# ProjekITS_5.net
KiCad netlist of a schematic drawn in EAGLE
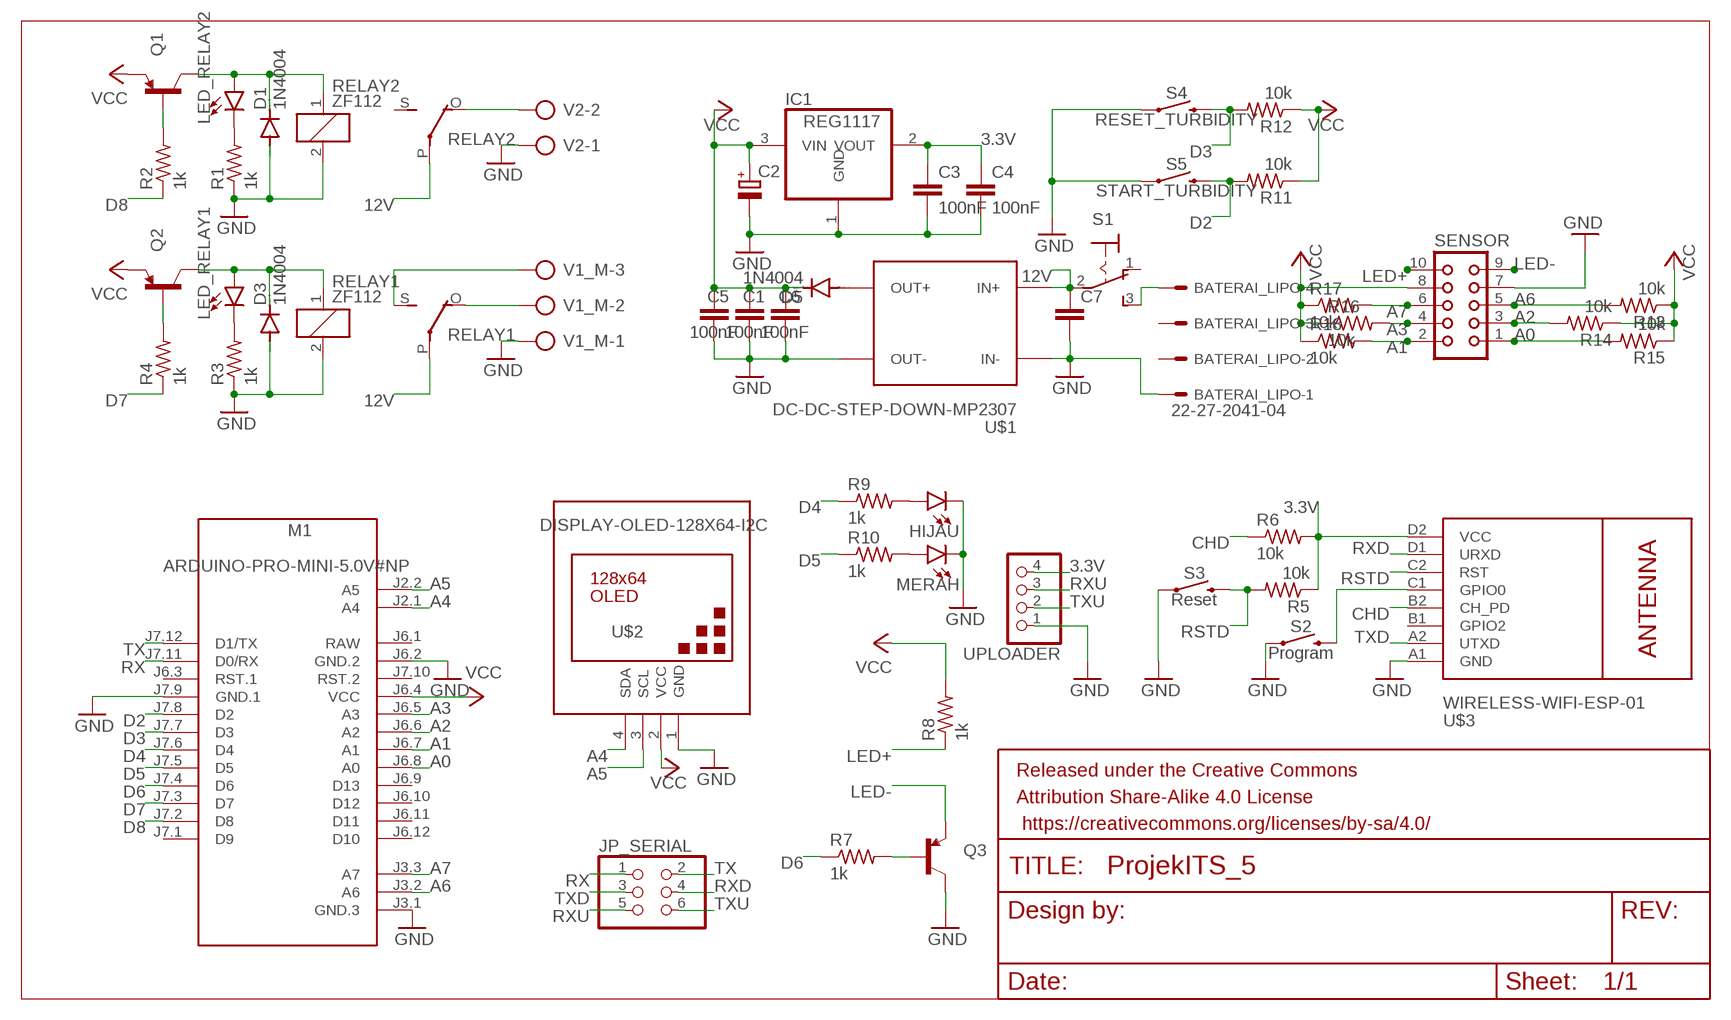
[diagram p0: schematic, sheet 1]

(export (version "E")
  (design (tool "Eeschema 10.0.6"))
  (components
    (comp (ref "BATERAI_LIPO")
      (value "22-27-2041-04")
      (footprint "eagle-import:6410-04")
      (fields (field (name "MF") "MOLEX"))
      (libsource (lib "eagle-import") (part "22-?-0427-2041"))
    )
    (comp (ref "C1")
      (value "100nF")
      (footprint "eagle-import:C0805K")
      (libsource (lib "eagle-import") (part "C-EUC0805K"))
    )
    (comp (ref "C2")
      (value "CPOL-EUCT3528")
      (footprint "eagle-import:CT3528")
      (libsource (lib "eagle-import") (part "CPOL-EUCT3528"))
    )
    (comp (ref "C3")
      (value "100nF")
      (footprint "eagle-import:C0805K")
      (libsource (lib "eagle-import") (part "C-EUC0805K"))
    )
    (comp (ref "C4")
      (value "100nF")
      (footprint "eagle-import:C0805K")
      (libsource (lib "eagle-import") (part "C-EUC0805K"))
    )
    (comp (ref "C5")
      (value "100nF")
      (footprint "eagle-import:C0805K")
      (libsource (lib "eagle-import") (part "C-EUC0805K"))
    )
    (comp (ref "C6")
      (value "100nF")
      (footprint "eagle-import:C0805K")
      (libsource (lib "eagle-import") (part "C-EUC0805K"))
    )
    (comp (ref "C7")
      (value "C-EU050-030X075")
      (footprint "eagle-import:C050-030X075")
      (libsource (lib "eagle-import") (part "C-EU050-030X075"))
    )
    (comp (ref "D1")
      (value "1N4004")
      (footprint "eagle-import:DO41-10")
      (libsource (lib "eagle-import") (part "1N4004"))
    )
    (comp (ref "D3")
      (value "1N4004")
      (footprint "eagle-import:DO41-10")
      (libsource (lib "eagle-import") (part "1N4004"))
    )
    (comp (ref "D5")
      (value "1N4004")
      (footprint "eagle-import:DO41-10")
      (libsource (lib "eagle-import") (part "1N4004"))
    )
    (comp (ref "FRAME1")
      (value "FRAME-LETTER")
      (footprint "eagle-import:CREATIVE_COMMONS")
      (libsource (lib "eagle-import") (part "FRAME-LETTER"))
    )
    (comp (ref "HIJAU")
      (value "LED5MM")
      (footprint "eagle-import:LED_5MM")
      (libsource (lib "eagle-import") (part "LED5MM"))
    )
    (comp (ref "IC1")
      (value "REG1117")
      (footprint "eagle-import:SOT223")
      (libsource (lib "eagle-import") (part "REG1117"))
    )
    (comp (ref "JP_SERIAL")
      (value "PINHD-2X3")
      (footprint "eagle-import:2X03")
      (libsource (lib "eagle-import") (part "PINHD-2X3"))
    )
    (comp (ref "LED_RELAY1")
      (value "LED3MM")
      (footprint "eagle-import:LED_3MM")
      (libsource (lib "eagle-import") (part "LED3MM"))
    )
    (comp (ref "LED_RELAY2")
      (value "LED3MM")
      (footprint "eagle-import:LED_3MM")
      (libsource (lib "eagle-import") (part "LED3MM"))
    )
    (comp (ref "M1")
      (value "ARDUINO-PRO-MINI-5.0V#NP")
      (footprint "eagle-import:ARDUINO-PRO-MINI#NP")
      (libsource (lib "eagle-import") (part "ARDUINO-PRO-MINI-#NP5.0V"))
    )
    (comp (ref "MERAH")
      (value "LED5MM")
      (footprint "eagle-import:LED_5MM")
      (libsource (lib "eagle-import") (part "LED5MM"))
    )
    (comp (ref "Q1")
      (value "TRANSISTOR_PNPSMD")
      (footprint "eagle-import:SOT23-3")
      (libsource (lib "eagle-import") (part "TRANSISTOR_PNPSMD"))
    )
    (comp (ref "Q2")
      (value "TRANSISTOR_PNPSMD")
      (footprint "eagle-import:SOT23-3")
      (libsource (lib "eagle-import") (part "TRANSISTOR_PNPSMD"))
    )
    (comp (ref "Q3")
      (value "TRANSISTOR_PNPSMD")
      (footprint "eagle-import:SOT23-3")
      (libsource (lib "eagle-import") (part "TRANSISTOR_PNPSMD"))
    )
    (comp (ref "R1")
      (value "1k")
      (footprint "eagle-import:R0805")
      (libsource (lib "eagle-import") (part "R-US_R0805"))
    )
    (comp (ref "R2")
      (value "1k")
      (footprint "eagle-import:R0805")
      (libsource (lib "eagle-import") (part "R-US_R0805"))
    )
    (comp (ref "R3")
      (value "1k")
      (footprint "eagle-import:R0805")
      (libsource (lib "eagle-import") (part "R-US_R0805"))
    )
    (comp (ref "R4")
      (value "1k")
      (footprint "eagle-import:R0805")
      (libsource (lib "eagle-import") (part "R-US_R0805"))
    )
    (comp (ref "R5")
      (value "10k")
      (footprint "eagle-import:R0805")
      (libsource (lib "eagle-import") (part "R-US_R0805"))
    )
    (comp (ref "R6")
      (value "10k")
      (footprint "eagle-import:R0805")
      (libsource (lib "eagle-import") (part "R-US_R0805"))
    )
    (comp (ref "R7")
      (value "1k")
      (footprint "eagle-import:R0805")
      (libsource (lib "eagle-import") (part "R-US_R0805"))
    )
    (comp (ref "R8")
      (value "1k")
      (footprint "eagle-import:R0805")
      (libsource (lib "eagle-import") (part "R-US_R0805"))
    )
    (comp (ref "R9")
      (value "1k")
      (footprint "eagle-import:R0805")
      (libsource (lib "eagle-import") (part "R-US_R0805"))
    )
    (comp (ref "R10")
      (value "1k")
      (footprint "eagle-import:R0805")
      (libsource (lib "eagle-import") (part "R-US_R0805"))
    )
    (comp (ref "R11")
      (value "10k")
      (footprint "eagle-import:R0805")
      (libsource (lib "eagle-import") (part "R-US_R0805"))
    )
    (comp (ref "R12")
      (value "10k")
      (footprint "eagle-import:R0805")
      (libsource (lib "eagle-import") (part "R-US_R0805"))
    )
    (comp (ref "R13")
      (value "10k")
      (footprint "eagle-import:R0805")
      (libsource (lib "eagle-import") (part "R-US_R0805"))
    )
    (comp (ref "R14")
      (value "10k")
      (footprint "eagle-import:R0805")
      (libsource (lib "eagle-import") (part "R-US_R0805"))
    )
    (comp (ref "R15")
      (value "10k")
      (footprint "eagle-import:R0805")
      (libsource (lib "eagle-import") (part "R-US_R0805"))
    )
    (comp (ref "R16")
      (value "10k")
      (footprint "eagle-import:R0805")
      (libsource (lib "eagle-import") (part "R-US_R0805"))
    )
    (comp (ref "R17")
      (value "10k")
      (footprint "eagle-import:R0805")
      (libsource (lib "eagle-import") (part "R-US_R0805"))
    )
    (comp (ref "R18")
      (value "10k")
      (footprint "eagle-import:R0805")
      (libsource (lib "eagle-import") (part "R-US_R0805"))
    )
    (comp (ref "RELAY1")
      (value "ZF112")
      (footprint "eagle-import:ZF112")
      (libsource (lib "eagle-import") (part "ZF112"))
    )
    (comp (ref "RELAY2")
      (value "ZF112")
      (footprint "eagle-import:ZF112")
      (libsource (lib "eagle-import") (part "ZF112"))
    )
    (comp (ref "S1")
      (value "320-916")
      (footprint "eagle-import:320-916")
      (libsource (lib "eagle-import") (part "320-916"))
    )
    (comp (ref "S2")
      (value "Program")
      (footprint "eagle-import:TACTILE_SWITCH_PTH_6.0MM")
      (libsource (lib "eagle-import") (part "MOMENTARY-SWITCH-SPST-PTH-6.0MM"))
    )
    (comp (ref "S3")
      (value "Reset")
      (footprint "eagle-import:TACTILE_SWITCH_PTH_6.0MM")
      (libsource (lib "eagle-import") (part "MOMENTARY-SWITCH-SPST-PTH-6.0MM"))
    )
    (comp (ref "S4")
      (value "RESET_TURBIDITY")
      (footprint "eagle-import:TACTILE_SWITCH_PTH_6.0MM")
      (libsource (lib "eagle-import") (part "MOMENTARY-SWITCH-SPST-PTH-6.0MM"))
    )
    (comp (ref "S5")
      (value "START_TURBIDITY")
      (footprint "eagle-import:TACTILE_SWITCH_PTH_6.0MM")
      (libsource (lib "eagle-import") (part "MOMENTARY-SWITCH-SPST-PTH-6.0MM"))
    )
    (comp (ref "SENSOR")
      (value "CON10L")
      (footprint "eagle-import:CON10L")
      (libsource (lib "eagle-import") (part "CON10L"))
    )
    (comp (ref "U$1")
      (value "DC-DC-STEP-DOWN-MP2307")
      (footprint "eagle-import:DC-DC-STEP-DOWN-MP2307")
      (libsource (lib "eagle-import") (part "DC-DC-STEP-DOWN-MP2307"))
    )
    (comp (ref "U$2")
      (value "DISPLAY-OLED-128X64-I2C")
      (footprint "eagle-import:DISPLAY-OLED-128X64-I2C")
      (libsource (lib "eagle-import") (part "DISPLAY-OLED-128X64-I2C"))
    )
    (comp (ref "U$3")
      (value "WIRELESS-WIFI-ESP-01")
      (footprint "eagle-import:WIRELESS-WIFI-ESP-01")
      (libsource (lib "eagle-import") (part "WIRELESS-WIFI-ESP-01"))
    )
    (comp (ref "UPLOADER")
      (value "PINHD-1X4/90")
      (footprint "eagle-import:1X04_90")
      (libsource (lib "eagle-import") (part "PINHD-1X4/90"))
    )
    (comp (ref "V1_M")
      (value "AK500/3")
      (footprint "eagle-import:AK500_3")
      (libsource (lib "eagle-import") (part "AK500/3"))
    )
    (comp (ref "V2")
      (value "AK500/2")
      (footprint "eagle-import:AK500_2")
      (libsource (lib "eagle-import") (part "AK500/2"))
    )
  )
  (nets
    (net (code "1") (name "/3.3V") (class "Default")
      (node (ref "C3") (pin "1") (pinfunction "1_1") (pintype "passive"))
      (node (ref "C4") (pin "1") (pinfunction "1_1") (pintype "passive"))
      (node (ref "IC1") (pin "2") (pinfunction "VOUT_2") (pintype "output"))
      (node (ref "R5") (pin "1") (pinfunction "1_1") (pintype "passive"))
      (node (ref "R6") (pin "2") (pinfunction "2_2") (pintype "passive"))
      (node (ref "U$3") (pin "D2") (pinfunction "VCC_D2") (pintype "power_in"))
      (node (ref "UPLOADER") (pin "4") (pinfunction "4_4") (pintype "passive"))
    )
    (net (code "2") (name "/12V") (class "Default")
      (node (ref "C7") (pin "1") (pinfunction "1_1") (pintype "passive"))
      (node (ref "RELAY1") (pin "P") (pinfunction "P_P") (pintype "passive"))
      (node (ref "RELAY2") (pin "P") (pinfunction "P_P") (pintype "passive"))
      (node (ref "S1") (pin "2") (pinfunction "P_2") (pintype "passive"))
      (node (ref "U$1") (pin "IN+") (pinfunction "IN+_IN+") (pintype "bidirectional"))
    )
    (net (code "3") (name "/A0") (class "Default")
      (node (ref "M1") (pin "J6.8") (pinfunction "A0_J6.8") (pintype "bidirectional"))
      (node (ref "R15") (pin "2") (pinfunction "2_2") (pintype "passive"))
      (node (ref "SENSOR") (pin "1") (pinfunction "1_1") (pintype "passive"))
    )
    (net (code "4") (name "/A1") (class "Default")
      (node (ref "M1") (pin "J6.7") (pinfunction "A1_J6.7") (pintype "bidirectional"))
      (node (ref "R18") (pin "2") (pinfunction "2_2") (pintype "passive"))
      (node (ref "SENSOR") (pin "2") (pinfunction "2_2") (pintype "passive"))
    )
    (net (code "5") (name "/A2") (class "Default")
      (node (ref "M1") (pin "J6.6") (pinfunction "A2_J6.6") (pintype "bidirectional"))
      (node (ref "R14") (pin "2") (pinfunction "2_2") (pintype "passive"))
      (node (ref "SENSOR") (pin "3") (pinfunction "3_3") (pintype "passive"))
    )
    (net (code "6") (name "/A3") (class "Default")
      (node (ref "M1") (pin "J6.5") (pinfunction "A3_J6.5") (pintype "bidirectional"))
      (node (ref "R16") (pin "2") (pinfunction "2_2") (pintype "passive"))
      (node (ref "SENSOR") (pin "4") (pinfunction "4_4") (pintype "passive"))
    )
    (net (code "7") (name "/A4") (class "Default")
      (node (ref "M1") (pin "J2.1") (pinfunction "A4_J2.1") (pintype "bidirectional"))
      (node (ref "U$2") (pin "4") (pinfunction "SDA_4") (pintype "bidirectional"))
    )
    (net (code "8") (name "/A5") (class "Default")
      (node (ref "M1") (pin "J2.2") (pinfunction "A5_J2.2") (pintype "bidirectional"))
      (node (ref "U$2") (pin "3") (pinfunction "SCL_3") (pintype "bidirectional"))
    )
    (net (code "9") (name "/A6") (class "Default")
      (node (ref "M1") (pin "J3.2") (pinfunction "A6_J3.2") (pintype "bidirectional"))
      (node (ref "R13") (pin "2") (pinfunction "2_2") (pintype "passive"))
      (node (ref "SENSOR") (pin "5") (pinfunction "5_5") (pintype "passive"))
    )
    (net (code "10") (name "/A7") (class "Default")
      (node (ref "M1") (pin "J3.3") (pinfunction "A7_J3.3") (pintype "bidirectional"))
      (node (ref "R17") (pin "2") (pinfunction "2_2") (pintype "passive"))
      (node (ref "SENSOR") (pin "6") (pinfunction "6_6") (pintype "passive"))
    )
    (net (code "11") (name "/CHD") (class "Default")
      (node (ref "R6") (pin "1") (pinfunction "1_1") (pintype "passive"))
      (node (ref "U$3") (pin "B2") (pinfunction "CH_PD_B2") (pintype "bidirectional"))
    )
    (net (code "12") (name "/D2") (class "Default")
      (node (ref "M1") (pin "J7.8") (pinfunction "D2_J7.8") (pintype "bidirectional"))
      (node (ref "R11") (pin "2") (pinfunction "2_2") (pintype "passive"))
      (node (ref "S5") (pin "3") (pinfunction "2_3") (pintype "passive"))
    )
    (net (code "13") (name "/D3") (class "Default")
      (node (ref "M1") (pin "J7.7") (pinfunction "D3_J7.7") (pintype "bidirectional"))
      (node (ref "R12") (pin "2") (pinfunction "2_2") (pintype "passive"))
      (node (ref "S4") (pin "3") (pinfunction "2_3") (pintype "passive"))
    )
    (net (code "14") (name "/D4") (class "Default")
      (node (ref "M1") (pin "J7.6") (pinfunction "D4_J7.6") (pintype "bidirectional"))
      (node (ref "R9") (pin "1") (pinfunction "1_1") (pintype "passive"))
    )
    (net (code "15") (name "/D5") (class "Default")
      (node (ref "M1") (pin "J7.5") (pinfunction "D5_J7.5") (pintype "bidirectional"))
      (node (ref "R10") (pin "1") (pinfunction "1_1") (pintype "passive"))
    )
    (net (code "16") (name "/D6") (class "Default")
      (node (ref "M1") (pin "J7.4") (pinfunction "D6_J7.4") (pintype "bidirectional"))
      (node (ref "R7") (pin "1") (pinfunction "1_1") (pintype "passive"))
    )
    (net (code "17") (name "/D7") (class "Default")
      (node (ref "M1") (pin "J7.3") (pinfunction "D7_J7.3") (pintype "bidirectional"))
      (node (ref "R4") (pin "1") (pinfunction "1_1") (pintype "passive"))
    )
    (net (code "18") (name "/D8") (class "Default")
      (node (ref "M1") (pin "J7.2") (pinfunction "D8_J7.2") (pintype "bidirectional"))
      (node (ref "R2") (pin "1") (pinfunction "1_1") (pintype "passive"))
    )
    (net (code "19") (name "/LED+") (class "Default")
      (node (ref "R8") (pin "1") (pinfunction "1_1") (pintype "passive"))
      (node (ref "SENSOR") (pin "10") (pinfunction "10_10") (pintype "passive"))
    )
    (net (code "20") (name "/LED-") (class "Default")
      (node (ref "Q3") (pin "2") (pinfunction "E_2") (pintype "passive"))
      (node (ref "SENSOR") (pin "9") (pinfunction "9_9") (pintype "passive"))
    )
    (net (code "21") (name "/RAW") (class "Default")
      (node (ref "M1") (pin "J6.1") (pinfunction "RAW_J6.1") (pintype "power_in"))
    )
    (net (code "22") (name "/RSTD") (class "Default")
      (node (ref "R5") (pin "2") (pinfunction "2_2") (pintype "passive"))
      (node (ref "S3") (pin "3") (pinfunction "2_3") (pintype "passive"))
      (node (ref "U$3") (pin "C2") (pinfunction "RST_C2") (pintype "bidirectional"))
    )
    (net (code "23") (name "/RX") (class "Default")
      (node (ref "JP_SERIAL") (pin "1") (pinfunction "1_1") (pintype "passive"))
      (node (ref "M1") (pin "J7.11") (pinfunction "D0/RX_J7.11") (pintype "bidirectional"))
    )
    (net (code "24") (name "/RXD") (class "Default")
      (node (ref "JP_SERIAL") (pin "4") (pinfunction "4_4") (pintype "passive"))
      (node (ref "U$3") (pin "D1") (pinfunction "URXD_D1") (pintype "bidirectional"))
    )
    (net (code "25") (name "/RXU") (class "Default")
      (node (ref "JP_SERIAL") (pin "5") (pinfunction "5_5") (pintype "passive"))
      (node (ref "UPLOADER") (pin "3") (pinfunction "3_3") (pintype "passive"))
    )
    (net (code "26") (name "/TX") (class "Default")
      (node (ref "JP_SERIAL") (pin "2") (pinfunction "2_2") (pintype "passive"))
      (node (ref "M1") (pin "J7.12") (pinfunction "D1/TX_J7.12") (pintype "bidirectional"))
    )
    (net (code "27") (name "/TXD") (class "Default")
      (node (ref "JP_SERIAL") (pin "3") (pinfunction "3_3") (pintype "passive"))
      (node (ref "U$3") (pin "A2") (pinfunction "UTXD_A2") (pintype "bidirectional"))
    )
    (net (code "28") (name "/TXU") (class "Default")
      (node (ref "JP_SERIAL") (pin "6") (pinfunction "6_6") (pintype "passive"))
      (node (ref "UPLOADER") (pin "2") (pinfunction "2_2") (pintype "passive"))
    )
    (net (code "29") (name "GND") (class "Default")
      (node (ref "BATERAI_LIPO") (pin "1") (pinfunction "S_1") (pintype "passive"))
      (node (ref "C1") (pin "2") (pinfunction "2_2") (pintype "passive"))
      (node (ref "C2") (pin "-") (pinfunction "-_-") (pintype "passive"))
      (node (ref "C3") (pin "2") (pinfunction "2_2") (pintype "passive"))
      (node (ref "C4") (pin "2") (pinfunction "2_2") (pintype "passive"))
      (node (ref "C5") (pin "2") (pinfunction "2_2") (pintype "passive"))
      (node (ref "C6") (pin "2") (pinfunction "2_2") (pintype "passive"))
      (node (ref "C7") (pin "2") (pinfunction "2_2") (pintype "passive"))
      (node (ref "D1") (pin "A") (pinfunction "A_A") (pintype "passive"))
      (node (ref "D3") (pin "A") (pinfunction "A_A") (pintype "passive"))
      (node (ref "HIJAU") (pin "K") (pinfunction "C_K") (pintype "passive"))
      (node (ref "IC1") (pin "1") (pinfunction "GND_1") (pintype "power_in"))
      (node (ref "M1") (pin "J3.1") (pinfunction "GND.3_J3.1") (pintype "bidirectional"))
      (node (ref "M1") (pin "J6.2") (pinfunction "GND.2_J6.2") (pintype "power_in"))
      (node (ref "M1") (pin "J7.9") (pinfunction "GND.1_J7.9") (pintype "power_in"))
      (node (ref "MERAH") (pin "K") (pinfunction "C_K") (pintype "passive"))
      (node (ref "Q3") (pin "3") (pinfunction "C_3") (pintype "passive"))
      (node (ref "R1") (pin "1") (pinfunction "1_1") (pintype "passive"))
      (node (ref "R3") (pin "1") (pinfunction "1_1") (pintype "passive"))
      (node (ref "RELAY1") (pin "2") (pinfunction "2_2") (pintype "passive"))
      (node (ref "RELAY2") (pin "2") (pinfunction "2_2") (pintype "passive"))
      (node (ref "S2") (pin "1") (pinfunction "1_1") (pintype "passive"))
      (node (ref "S3") (pin "1") (pinfunction "1_1") (pintype "passive"))
      (node (ref "S4") (pin "1") (pinfunction "1_1") (pintype "passive"))
      (node (ref "S5") (pin "1") (pinfunction "1_1") (pintype "passive"))
      (node (ref "SENSOR") (pin "7") (pinfunction "7_7") (pintype "passive"))
      (node (ref "U$1") (pin "IN-") (pinfunction "IN-_IN-") (pintype "bidirectional"))
      (node (ref "U$1") (pin "OUT-") (pinfunction "OUT-_OUT-") (pintype "bidirectional"))
      (node (ref "U$2") (pin "1") (pinfunction "GND_1") (pintype "power_in"))
      (node (ref "U$3") (pin "A1") (pinfunction "GND_A1") (pintype "power_in"))
      (node (ref "UPLOADER") (pin "1") (pinfunction "1_1") (pintype "passive"))
      (node (ref "V1_M") (pin "1") (pinfunction "KL_1") (pintype "passive"))
      (node (ref "V2") (pin "1") (pinfunction "KL_1") (pintype "passive"))
    )
    (net (code "30") (name "Net-(BATERAI_LIPOD-S)") (class "Default")
      (node (ref "BATERAI_LIPO") (pin "4") (pinfunction "S_4") (pintype "passive"))
      (node (ref "S1") (pin "3") (pinfunction "S_3") (pintype "passive"))
    )
    (net (code "31") (name "Net-(D5-PadA)") (class "Default")
      (node (ref "D5") (pin "A") (pinfunction "A_A") (pintype "passive"))
      (node (ref "U$1") (pin "OUT+") (pinfunction "OUT+_OUT+") (pintype "bidirectional"))
    )
    (net (code "32") (name "Net-(HIJAU-PadA)") (class "Default")
      (node (ref "HIJAU") (pin "A") (pinfunction "A_A") (pintype "passive"))
      (node (ref "R9") (pin "2") (pinfunction "2_2") (pintype "passive"))
    )
    (net (code "33") (name "Net-(LED_RELAY1-C)") (class "Default")
      (node (ref "LED_RELAY1") (pin "K") (pinfunction "C_K") (pintype "passive"))
      (node (ref "R3") (pin "2") (pinfunction "2_2") (pintype "passive"))
    )
    (net (code "34") (name "Net-(LED_RELAY2-C)") (class "Default")
      (node (ref "LED_RELAY2") (pin "K") (pinfunction "C_K") (pintype "passive"))
      (node (ref "R1") (pin "2") (pinfunction "2_2") (pintype "passive"))
    )
    (net (code "35") (name "Net-(MERAH-PadA)") (class "Default")
      (node (ref "MERAH") (pin "A") (pinfunction "A_A") (pintype "passive"))
      (node (ref "R10") (pin "2") (pinfunction "2_2") (pintype "passive"))
    )
    (net (code "36") (name "Net-(Q1-B)") (class "Default")
      (node (ref "Q1") (pin "1") (pinfunction "B_1") (pintype "passive"))
      (node (ref "R2") (pin "2") (pinfunction "2_2") (pintype "passive"))
    )
    (net (code "37") (name "Net-(Q1-C)") (class "Default")
      (node (ref "D1") (pin "C") (pinfunction "C_C") (pintype "passive"))
      (node (ref "LED_RELAY2") (pin "A") (pinfunction "A_A") (pintype "passive"))
      (node (ref "Q1") (pin "3") (pinfunction "C_3") (pintype "passive"))
      (node (ref "RELAY2") (pin "1") (pinfunction "1_1") (pintype "passive"))
    )
    (net (code "38") (name "Net-(Q2-B)") (class "Default")
      (node (ref "Q2") (pin "1") (pinfunction "B_1") (pintype "passive"))
      (node (ref "R4") (pin "2") (pinfunction "2_2") (pintype "passive"))
    )
    (net (code "39") (name "Net-(Q2-C)") (class "Default")
      (node (ref "D3") (pin "C") (pinfunction "C_C") (pintype "passive"))
      (node (ref "LED_RELAY1") (pin "A") (pinfunction "A_A") (pintype "passive"))
      (node (ref "Q2") (pin "3") (pinfunction "C_3") (pintype "passive"))
      (node (ref "RELAY1") (pin "1") (pinfunction "1_1") (pintype "passive"))
    )
    (net (code "40") (name "Net-(Q3-B)") (class "Default")
      (node (ref "Q3") (pin "1") (pinfunction "B_1") (pintype "passive"))
      (node (ref "R7") (pin "2") (pinfunction "2_2") (pintype "passive"))
    )
    (net (code "41") (name "Net-(S2-2)") (class "Default")
      (node (ref "S2") (pin "3") (pinfunction "2_3") (pintype "passive"))
      (node (ref "U$3") (pin "C1") (pinfunction "GPIO0_C1") (pintype "bidirectional"))
    )
    (net (code "42") (name "Net-(V1_MB-KL)") (class "Default")
      (node (ref "RELAY1") (pin "O") (pinfunction "O_O") (pintype "passive"))
      (node (ref "V1_M") (pin "2") (pinfunction "KL_2") (pintype "passive"))
    )
    (net (code "43") (name "Net-(V1_MC-KL)") (class "Default")
      (node (ref "RELAY1") (pin "S") (pinfunction "S_S") (pintype "passive"))
      (node (ref "V1_M") (pin "3") (pinfunction "KL_3") (pintype "passive"))
    )
    (net (code "44") (name "Net-(V2B-KL)") (class "Default")
      (node (ref "RELAY2") (pin "O") (pinfunction "O_O") (pintype "passive"))
      (node (ref "V2") (pin "2") (pinfunction "KL_2") (pintype "passive"))
    )
    (net (code "45") (name "VCC") (class "Default")
      (node (ref "C1") (pin "1") (pinfunction "1_1") (pintype "passive"))
      (node (ref "C2") (pin "+") (pinfunction "+_+") (pintype "passive"))
      (node (ref "C5") (pin "1") (pinfunction "1_1") (pintype "passive"))
      (node (ref "C6") (pin "1") (pinfunction "1_1") (pintype "passive"))
      (node (ref "D5") (pin "C") (pinfunction "C_C") (pintype "passive"))
      (node (ref "IC1") (pin "3") (pinfunction "VIN_3") (pintype "input"))
      (node (ref "M1") (pin "J6.4") (pinfunction "VCC_J6.4") (pintype "power_in"))
      (node (ref "Q1") (pin "2") (pinfunction "E_2") (pintype "passive"))
      (node (ref "Q2") (pin "2") (pinfunction "E_2") (pintype "passive"))
      (node (ref "R11") (pin "1") (pinfunction "1_1") (pintype "passive"))
      (node (ref "R12") (pin "1") (pinfunction "1_1") (pintype "passive"))
      (node (ref "R13") (pin "1") (pinfunction "1_1") (pintype "passive"))
      (node (ref "R14") (pin "1") (pinfunction "1_1") (pintype "passive"))
      (node (ref "R15") (pin "1") (pinfunction "1_1") (pintype "passive"))
      (node (ref "R16") (pin "1") (pinfunction "1_1") (pintype "passive"))
      (node (ref "R17") (pin "1") (pinfunction "1_1") (pintype "passive"))
      (node (ref "R18") (pin "1") (pinfunction "1_1") (pintype "passive"))
      (node (ref "R8") (pin "2") (pinfunction "2_2") (pintype "passive"))
      (node (ref "SENSOR") (pin "8") (pinfunction "8_8") (pintype "passive"))
      (node (ref "U$2") (pin "2") (pinfunction "VCC_2") (pintype "power_in"))
    )
    (net (code "46") (name "unconnected-(BATERAI_LIPOB-S-Pad2)") (class "Default")
      (node (ref "BATERAI_LIPO") (pin "2") (pinfunction "S_2") (pintype "passive"))
    )
    (net (code "47") (name "unconnected-(BATERAI_LIPOC-S-Pad3)") (class "Default")
      (node (ref "BATERAI_LIPO") (pin "3") (pinfunction "S_3") (pintype "passive"))
    )
    (net (code "48") (name "unconnected-(M1-D9-PadJ7.1)") (class "Default")
      (node (ref "M1") (pin "J7.1") (pinfunction "D9_J7.1") (pintype "bidirectional"))
    )
    (net (code "49") (name "unconnected-(M1-D10-PadJ6.12)") (class "Default")
      (node (ref "M1") (pin "J6.12") (pinfunction "D10_J6.12") (pintype "bidirectional"))
    )
    (net (code "50") (name "unconnected-(M1-D11-PadJ6.11)") (class "Default")
      (node (ref "M1") (pin "J6.11") (pinfunction "D11_J6.11") (pintype "bidirectional"))
    )
    (net (code "51") (name "unconnected-(M1-D12-PadJ6.10)") (class "Default")
      (node (ref "M1") (pin "J6.10") (pinfunction "D12_J6.10") (pintype "bidirectional"))
    )
    (net (code "52") (name "unconnected-(M1-D13-PadJ6.9)") (class "Default")
      (node (ref "M1") (pin "J6.9") (pinfunction "D13_J6.9") (pintype "bidirectional"))
    )
    (net (code "53") (name "unconnected-(M1-RST.1-PadJ6.3)") (class "Default")
      (node (ref "M1") (pin "J6.3") (pinfunction "RST.1_J6.3") (pintype "bidirectional"))
    )
    (net (code "54") (name "unconnected-(M1-RST.2-PadJ7.10)") (class "Default")
      (node (ref "M1") (pin "J7.10") (pinfunction "RST.2_J7.10") (pintype "bidirectional"))
    )
    (net (code "55") (name "unconnected-(RELAY2-PadS)") (class "Default")
      (node (ref "RELAY2") (pin "S") (pinfunction "S_S") (pintype "passive"))
    )
    (net (code "56") (name "unconnected-(S1-O-Pad1)") (class "Default")
      (node (ref "S1") (pin "1") (pinfunction "O_1") (pintype "passive"))
    )
    (net (code "57") (name "unconnected-(U$3-GPIO2-PadB1)") (class "Default")
      (node (ref "U$3") (pin "B1") (pinfunction "GPIO2_B1") (pintype "bidirectional"))
    )
  )
)
